# ET-AIO.net
KiCad netlist of a schematic drawn in Altium Designer
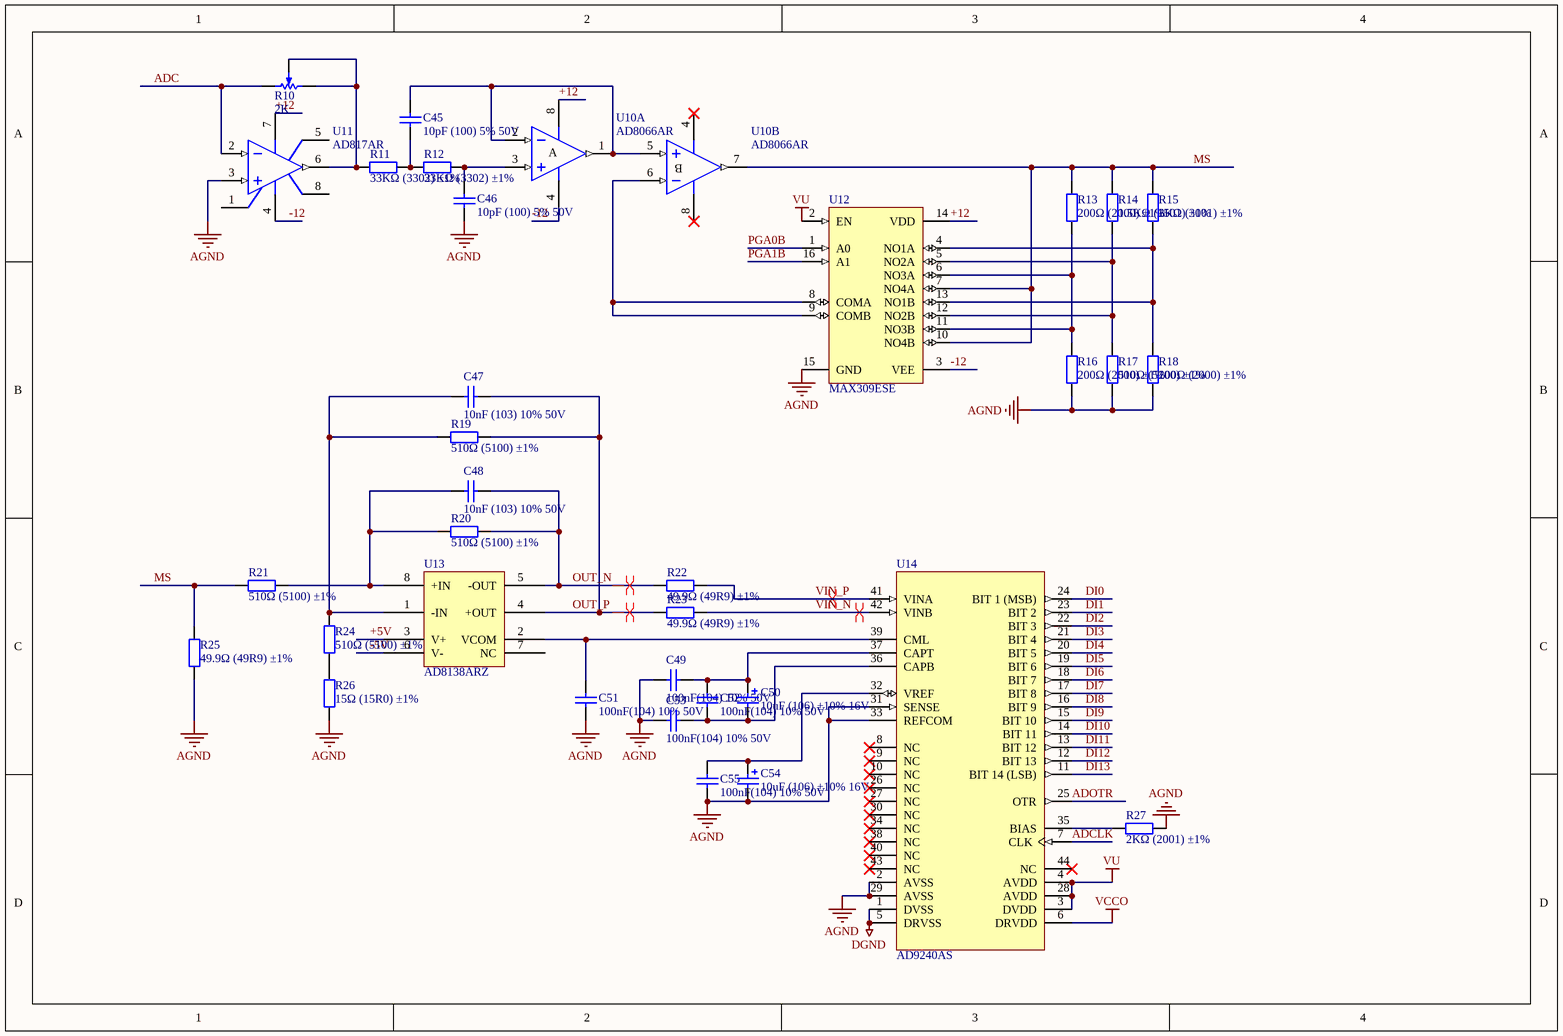
[diagram p0: ET-AIO.SchDoc]

(export (version "E")
  (design (tool "Eeschema 10.0.6"))
  (components
    (comp (ref "C45")
      (value "10pF (100) 5% 50V")
      (footprint "LC-0805_C")
      (description "贴片电容")
      (libsource (lib "Miscellaneous Devices LC") (part "0805 10pF (100) 5% 50V"))
    )
    (comp (ref "C46")
      (value "10pF (100) 5% 50V")
      (footprint "LC-0805_C")
      (description "贴片电容")
      (libsource (lib "Miscellaneous Devices LC") (part "0805 10pF (100) 5% 50V"))
    )
    (comp (ref "C47")
      (value "10nF (103) 10% 50V")
      (footprint "LC-0805_C")
      (description "贴片电容")
      (libsource (lib "Miscellaneous Devices LC") (part "0805 10nF (103) 10% 50V"))
    )
    (comp (ref "C48")
      (value "10nF (103) 10% 50V")
      (footprint "LC-0805_C")
      (description "贴片电容")
      (libsource (lib "Miscellaneous Devices LC") (part "0805 10nF (103) 10% 50V"))
    )
    (comp (ref "C49")
      (value "100nF(104) 10% 50V")
      (footprint "LC-0805_C")
      (description "贴片电容")
      (libsource (lib "Miscellaneous Devices LC") (part "0805 100nF(104) 10% 50V"))
    )
    (comp (ref "C50")
      (value "10uF (106) ±10% 16V")
      (footprint "LC-CASE-A_3216")
      (description "钽电容")
      (libsource (lib "Miscellaneous Devices LC") (part "3216 10uF (106) 10% 16V"))
    )
    (comp (ref "C51")
      (value "100nF(104) 10% 50V")
      (footprint "LC-0805_C")
      (description "贴片电容")
      (libsource (lib "Miscellaneous Devices LC") (part "0805 100nF(104) 10% 50V"))
    )
    (comp (ref "C52")
      (value "100nF(104) 10% 50V")
      (footprint "LC-0805_C")
      (description "贴片电容")
      (libsource (lib "Miscellaneous Devices LC") (part "0805 100nF(104) 10% 50V"))
    )
    (comp (ref "C53")
      (value "100nF(104) 10% 50V")
      (footprint "LC-0805_C")
      (description "贴片电容")
      (libsource (lib "Miscellaneous Devices LC") (part "0805 100nF(104) 10% 50V"))
    )
    (comp (ref "C54")
      (value "10uF (106) ±10% 16V")
      (footprint "LC-CASE-A_3216")
      (description "钽电容")
      (libsource (lib "Miscellaneous Devices LC") (part "3216 10uF (106) 10% 16V"))
    )
    (comp (ref "C55")
      (value "100nF(104) 10% 50V")
      (footprint "LC-0805_C")
      (description "贴片电容")
      (libsource (lib "Miscellaneous Devices LC") (part "0805 100nF(104) 10% 50V"))
    )
    (comp (ref "R10")
      (value "2K")
      (footprint "POT4MM-2")
      (description "Square Trimming Potentiometer")
      (fields (field (name "PUBLISHER") "Altium Limited"))
      (libsource (lib "Miscellaneous Devices") (part "RPot SM"))
    )
    (comp (ref "R11")
      (value "33KΩ (3302) ±1%")
      (footprint "LC-0805_R")
      (description "贴片电阻")
      (libsource (lib "Miscellaneous Devices LC") (part "0805 33KΩ (3302) 1%"))
    )
    (comp (ref "R12")
      (value "33KΩ (3302) ±1%")
      (footprint "LC-0805_R")
      (description "贴片电阻")
      (libsource (lib "Miscellaneous Devices LC") (part "0805 33KΩ (3302) 1%"))
    )
    (comp (ref "R13")
      (value "200Ω (2000) ±1%")
      (footprint "LC-0805_R")
      (description "贴片电阻")
      (libsource (lib "Miscellaneous Devices LC") (part "0805 200Ω (2000) 1%"))
    )
    (comp (ref "R14")
      (value "1.5KΩ (1501) ±1%")
      (footprint "LC-0805_R")
      (description "贴片电阻")
      (libsource (lib "Miscellaneous Devices LC") (part "0805 1.5KΩ (1501) 1%"))
    )
    (comp (ref "R15")
      (value "3KΩ (3001) ±1%")
      (footprint "LC-0805_R")
      (description "贴片电阻")
      (libsource (lib "Miscellaneous Devices LC") (part "0805 3KΩ (3001) 1%"))
    )
    (comp (ref "R16")
      (value "200Ω (2000) ±1%")
      (footprint "LC-0805_R")
      (description "贴片电阻")
      (libsource (lib "Miscellaneous Devices LC") (part "0805 200Ω (2000) 1%"))
    )
    (comp (ref "R17")
      (value "510Ω (5100) ±1%")
      (footprint "LC-0805_R")
      (description "贴片电阻")
      (libsource (lib "") (part "0805 510Ω (5100) 1%_1"))
    )
    (comp (ref "R18")
      (value "200Ω (2000) ±1%")
      (footprint "LC-0805_R")
      (description "贴片电阻")
      (libsource (lib "Miscellaneous Devices LC") (part "0805 200Ω (2000) 1%"))
    )
    (comp (ref "R19")
      (value "510Ω (5100) ±1%")
      (footprint "LC-0805_R")
      (description "贴片电阻")
      (libsource (lib "Miscellaneous Devices LC") (part "0805 510Ω (5100) 1%"))
    )
    (comp (ref "R20")
      (value "510Ω (5100) ±1%")
      (footprint "LC-0805_R")
      (description "贴片电阻")
      (libsource (lib "Miscellaneous Devices LC") (part "0805 510Ω (5100) 1%"))
    )
    (comp (ref "R21")
      (value "510Ω (5100) ±1%")
      (footprint "LC-0805_R")
      (description "贴片电阻")
      (libsource (lib "Miscellaneous Devices LC") (part "0805 510Ω (5100) 1%"))
    )
    (comp (ref "R22")
      (value "49.9Ω (49R9) ±1%")
      (footprint "LC-0805_R")
      (description "贴片电阻")
      (libsource (lib "Miscellaneous Devices LC") (part "0805 49.9Ω (49R9) 1%"))
    )
    (comp (ref "R23")
      (value "49.9Ω (49R9) ±1%")
      (footprint "LC-0805_R")
      (description "贴片电阻")
      (libsource (lib "Miscellaneous Devices LC") (part "0805 49.9Ω (49R9) 1%"))
    )
    (comp (ref "R24")
      (value "510Ω (5100) ±1%")
      (footprint "LC-0805_R")
      (description "贴片电阻")
      (libsource (lib "") (part "0805 510Ω (5100) 1%_1"))
    )
    (comp (ref "R25")
      (value "49.9Ω (49R9) ±1%")
      (footprint "LC-0805_R")
      (description "贴片电阻")
      (libsource (lib "") (part "0805 49.9Ω (49R9) 1%_1"))
    )
    (comp (ref "R26")
      (value "15Ω (15R0) ±1%")
      (footprint "LC-0805_R")
      (description "贴片电阻")
      (libsource (lib "Miscellaneous Devices LC") (part "0805 15Ω (15R0) 1%"))
    )
    (comp (ref "R27")
      (value "2KΩ (2001) ±1%")
      (footprint "LC-0805_R")
      (description "贴片电阻")
      (libsource (lib "Miscellaneous Devices LC") (part "0805 2KΩ (2001) 1%"))
    )
    (comp (ref "U10")
      (value "AD8066AR")
      (footprint "SO-8_N")
      (description "Low Cost, 300MHz Voltage Feedback Amplifier")
      (fields (field (name "PUBLISHER") "Altium Limited"))
      (libsource (lib "AD Operational Amplifier") (part "AD8056AR"))
    )
    (comp (ref "U11")
      (value "AD817AR")
      (footprint "mini-ET:SO-8_N")
      (description "High-Speed, Low-Power Wide Supply Range Amplifier")
      (fields (field (name "PUBLISHER") "Altium Limited"))
      (libsource (lib "AD Operational Amplifier") (part "AD817AR"))
    )
    (comp (ref "U12")
      (value "MAX309ESE")
      (footprint "mini-ET:NSO16_N")
      (description "Precision, Dual 4-Channel, High-Performance, CMOS Analog Multiplexer")
      (fields (field (name "PUBLISHER") "Altium Limited"))
      (libsource (lib "Maxim Logic Multiplexer") (part "MAX309ESE"))
    )
    (comp (ref "U13") (value "AD8138ARZ") (footprint "SO-8_N") (libsource (lib "AD8138") (part "AD8138ARZ")))
    (comp (ref "U14")
      (value "AD9240AS")
      (footprint "S-44-MQFP_N")
      (description "Complete 14-Bit, 10 MSPS Monolithic A/D Converter, 44-Pin MQFP, Industrial")
      (fields (field (name "PUBLISHER") "Altium Limited"))
      (libsource (lib "AD Converter Analog to Digital") (part "AD9240AS"))
    )
  )
  (nets
    (net (code "1") (name "/+5V") (class "Default")
      (node (ref "U13") (pin "3") (pinfunction "V+_3") (pintype "passive"))
    )
    (net (code "2") (name "/+12") (class "Default")
      (node (ref "U10") (pin "8") (pinfunction "V+_8") (pintype "power_in"))
      (node (ref "U11") (pin "7") (pinfunction "V+_7") (pintype "power_in"))
      (node (ref "U12") (pin "14") (pinfunction "VDD_14") (pintype "power_in"))
    )
    (net (code "3") (name "/-5V") (class "Default")
      (node (ref "U13") (pin "6") (pinfunction "V-_6") (pintype "passive"))
    )
    (net (code "4") (name "/-12") (class "Default")
      (node (ref "U10") (pin "4") (pinfunction "V-_4") (pintype "power_in"))
      (node (ref "U11") (pin "4") (pinfunction "V-_4") (pintype "power_in"))
      (node (ref "U12") (pin "3") (pinfunction "VEE_3") (pintype "power_in"))
    )
    (net (code "5") (name "/ADC") (class "Default")
      (node (ref "R10") (pin "CW") (pinfunction "+_CW") (pintype "passive"))
      (node (ref "U11") (pin "2") (pinfunction "IN-_2") (pintype "input"))
    )
    (net (code "6") (name "/ADCLK") (class "Default")
      (node (ref "U14") (pin "7") (pinfunction "CLK_7") (pintype "input"))
    )
    (net (code "7") (name "/ADOTR") (class "Default")
      (node (ref "U14") (pin "25") (pinfunction "OTR_25") (pintype "output"))
    )
    (net (code "8") (name "/DI0") (class "Default")
      (node (ref "U14") (pin "24") (pinfunction "BIT_1_(MSB)_24") (pintype "output"))
    )
    (net (code "9") (name "/DI1") (class "Default")
      (node (ref "U14") (pin "23") (pinfunction "BIT_2_23") (pintype "output"))
    )
    (net (code "10") (name "/DI2") (class "Default")
      (node (ref "U14") (pin "22") (pinfunction "BIT_3_22") (pintype "output"))
    )
    (net (code "11") (name "/DI3") (class "Default")
      (node (ref "U14") (pin "21") (pinfunction "BIT_4_21") (pintype "output"))
    )
    (net (code "12") (name "/DI4") (class "Default")
      (node (ref "U14") (pin "20") (pinfunction "BIT_5_20") (pintype "output"))
    )
    (net (code "13") (name "/DI5") (class "Default")
      (node (ref "U14") (pin "19") (pinfunction "BIT_6_19") (pintype "output"))
    )
    (net (code "14") (name "/DI6") (class "Default")
      (node (ref "U14") (pin "18") (pinfunction "BIT_7_18") (pintype "output"))
    )
    (net (code "15") (name "/DI7") (class "Default")
      (node (ref "U14") (pin "17") (pinfunction "BIT_8_17") (pintype "output"))
    )
    (net (code "16") (name "/DI8") (class "Default")
      (node (ref "U14") (pin "16") (pinfunction "BIT_9_16") (pintype "output"))
    )
    (net (code "17") (name "/DI9") (class "Default")
      (node (ref "U14") (pin "15") (pinfunction "BIT_10_15") (pintype "output"))
    )
    (net (code "18") (name "/DI10") (class "Default")
      (node (ref "U14") (pin "14") (pinfunction "BIT_11_14") (pintype "output"))
    )
    (net (code "19") (name "/DI11") (class "Default")
      (node (ref "U14") (pin "13") (pinfunction "BIT_12_13") (pintype "output"))
    )
    (net (code "20") (name "/DI12") (class "Default")
      (node (ref "U14") (pin "12") (pinfunction "BIT_13_12") (pintype "output"))
    )
    (net (code "21") (name "/DI13") (class "Default")
      (node (ref "U14") (pin "11") (pinfunction "BIT_14_(LSB)_11") (pintype "output"))
    )
    (net (code "22") (name "/MS") (class "Default")
      (node (ref "R13") (pin "2") (pinfunction "2_2") (pintype "passive"))
      (node (ref "R14") (pin "2") (pinfunction "2_2") (pintype "passive"))
      (node (ref "R15") (pin "2") (pinfunction "2_2") (pintype "passive"))
      (node (ref "R21") (pin "1") (pinfunction "1_1") (pintype "passive"))
      (node (ref "R25") (pin "2") (pinfunction "2_2") (pintype "passive"))
      (node (ref "U10") (pin "7") (pinfunction "OUT_7") (pintype "output"))
      (node (ref "U12") (pin "10") (pinfunction "NO4B_10") (pintype "bidirectional"))
      (node (ref "U12") (pin "7") (pinfunction "NO4A_7") (pintype "bidirectional"))
    )
    (net (code "23") (name "/OUT_N") (class "Default")
      (node (ref "C48") (pin "2") (pinfunction "2_2") (pintype "passive"))
      (node (ref "R20") (pin "2") (pinfunction "2_2") (pintype "passive"))
      (node (ref "R22") (pin "1") (pinfunction "1_1") (pintype "passive"))
      (node (ref "U13") (pin "5") (pinfunction "-OUT_5") (pintype "passive"))
    )
    (net (code "24") (name "/OUT_P") (class "Default")
      (node (ref "C47") (pin "2") (pinfunction "2_2") (pintype "passive"))
      (node (ref "R19") (pin "2") (pinfunction "2_2") (pintype "passive"))
      (node (ref "R23") (pin "1") (pinfunction "1_1") (pintype "passive"))
      (node (ref "U13") (pin "4") (pinfunction "+OUT_4") (pintype "passive"))
    )
    (net (code "25") (name "/PGA0B") (class "Default")
      (node (ref "U12") (pin "1") (pinfunction "A0_1") (pintype "input"))
    )
    (net (code "26") (name "/PGA1B") (class "Default")
      (node (ref "U12") (pin "16") (pinfunction "A1_16") (pintype "input"))
    )
    (net (code "27") (name "/VIN_N") (class "Default")
      (node (ref "R23") (pin "2") (pinfunction "2_2") (pintype "passive"))
      (node (ref "U14") (pin "42") (pinfunction "VINB_42") (pintype "input"))
    )
    (net (code "28") (name "/VIN_P") (class "Default")
      (node (ref "R22") (pin "2") (pinfunction "2_2") (pintype "passive"))
      (node (ref "U14") (pin "41") (pinfunction "VINA_41") (pintype "input"))
    )
    (net (code "29") (name "AGND") (class "Default")
      (node (ref "C46") (pin "1") (pinfunction "1_1") (pintype "passive"))
      (node (ref "C49") (pin "2") (pinfunction "2_2") (pintype "passive"))
      (node (ref "C51") (pin "1") (pinfunction "1_1") (pintype "passive"))
      (node (ref "C53") (pin "2") (pinfunction "2_2") (pintype "passive"))
      (node (ref "C54") (pin "2") (pinfunction "2_2") (pintype "passive"))
      (node (ref "C55") (pin "1") (pinfunction "1_1") (pintype "passive"))
      (node (ref "R16") (pin "1") (pinfunction "1_1") (pintype "passive"))
      (node (ref "R17") (pin "1") (pinfunction "1_1") (pintype "passive"))
      (node (ref "R18") (pin "1") (pinfunction "1_1") (pintype "passive"))
      (node (ref "R25") (pin "1") (pinfunction "1_1") (pintype "passive"))
      (node (ref "R26") (pin "1") (pinfunction "1_1") (pintype "passive"))
      (node (ref "R27") (pin "2") (pinfunction "2_2") (pintype "passive"))
      (node (ref "U11") (pin "3") (pinfunction "IN+_3") (pintype "input"))
      (node (ref "U12") (pin "15") (pinfunction "GND_15") (pintype "power_in"))
      (node (ref "U14") (pin "2") (pinfunction "AVSS_2") (pintype "power_in"))
      (node (ref "U14") (pin "29") (pinfunction "AVSS_29") (pintype "power_in"))
      (node (ref "U14") (pin "31") (pinfunction "SENSE_31") (pintype "input"))
      (node (ref "U14") (pin "33") (pinfunction "REFCOM_33") (pintype "power_in"))
    )
    (net (code "30") (name "DGND") (class "Default")
      (node (ref "U14") (pin "1") (pinfunction "DVSS_1") (pintype "power_in"))
      (node (ref "U14") (pin "5") (pinfunction "DRVSS_5") (pintype "power_in"))
    )
    (net (code "31") (name "Net-(C45-Pad1)") (class "Default")
      (node (ref "C45") (pin "1") (pinfunction "1_1") (pintype "passive"))
      (node (ref "R11") (pin "2") (pinfunction "2_2") (pintype "passive"))
      (node (ref "R12") (pin "1") (pinfunction "1_1") (pintype "passive"))
    )
    (net (code "32") (name "Net-(R10--)") (class "Default")
      (node (ref "R10") (pin "CCW") (pinfunction "-_CCW") (pintype "passive"))
      (node (ref "R10") (pin "W") (pinfunction "W_W") (pintype "passive"))
      (node (ref "R11") (pin "1") (pinfunction "1_1") (pintype "passive"))
      (node (ref "U11") (pin "6") (pinfunction "OUT_6") (pintype "output"))
    )
    (net (code "33") (name "Net-(R24-Pad1)") (class "Default")
      (node (ref "R24") (pin "1") (pinfunction "1_1") (pintype "passive"))
      (node (ref "R26") (pin "2") (pinfunction "2_2") (pintype "passive"))
    )
    (net (code "34") (name "Net-(U10A-IN+)") (class "Default")
      (node (ref "C46") (pin "2") (pinfunction "2_2") (pintype "passive"))
      (node (ref "R12") (pin "2") (pinfunction "2_2") (pintype "passive"))
      (node (ref "U10") (pin "3") (pinfunction "IN+_3") (pintype "input"))
    )
    (net (code "35") (name "Net-(U10A-IN-)") (class "Default")
      (node (ref "C45") (pin "2") (pinfunction "2_2") (pintype "passive"))
      (node (ref "U10") (pin "1") (pinfunction "OUT_1") (pintype "output"))
      (node (ref "U10") (pin "2") (pinfunction "IN-_2") (pintype "input"))
      (node (ref "U10") (pin "5") (pinfunction "IN+_5") (pintype "input"))
    )
    (net (code "36") (name "Net-(U10B-IN-)") (class "Default")
      (node (ref "U10") (pin "6") (pinfunction "IN-_6") (pintype "input"))
      (node (ref "U12") (pin "8") (pinfunction "COMA_8") (pintype "bidirectional"))
      (node (ref "U12") (pin "9") (pinfunction "COMB_9") (pintype "bidirectional"))
    )
    (net (code "37") (name "Net-(U12-NO1A)") (class "Default")
      (node (ref "R15") (pin "1") (pinfunction "1_1") (pintype "passive"))
      (node (ref "R18") (pin "2") (pinfunction "2_2") (pintype "passive"))
      (node (ref "U12") (pin "13") (pinfunction "NO1B_13") (pintype "bidirectional"))
      (node (ref "U12") (pin "4") (pinfunction "NO1A_4") (pintype "bidirectional"))
    )
    (net (code "38") (name "Net-(U12-NO2A)") (class "Default")
      (node (ref "R14") (pin "1") (pinfunction "1_1") (pintype "passive"))
      (node (ref "R17") (pin "2") (pinfunction "2_2") (pintype "passive"))
      (node (ref "U12") (pin "12") (pinfunction "NO2B_12") (pintype "bidirectional"))
      (node (ref "U12") (pin "5") (pinfunction "NO2A_5") (pintype "bidirectional"))
    )
    (net (code "39") (name "Net-(U12-NO3A)") (class "Default")
      (node (ref "R13") (pin "1") (pinfunction "1_1") (pintype "passive"))
      (node (ref "R16") (pin "2") (pinfunction "2_2") (pintype "passive"))
      (node (ref "U12") (pin "11") (pinfunction "NO3B_11") (pintype "bidirectional"))
      (node (ref "U12") (pin "6") (pinfunction "NO3A_6") (pintype "bidirectional"))
    )
    (net (code "40") (name "Net-(U13-+IN)") (class "Default")
      (node (ref "C48") (pin "1") (pinfunction "1_1") (pintype "passive"))
      (node (ref "R20") (pin "1") (pinfunction "1_1") (pintype "passive"))
      (node (ref "R21") (pin "2") (pinfunction "2_2") (pintype "passive"))
      (node (ref "U13") (pin "8") (pinfunction "+IN_8") (pintype "passive"))
    )
    (net (code "41") (name "Net-(U13--IN)") (class "Default")
      (node (ref "C47") (pin "1") (pinfunction "1_1") (pintype "passive"))
      (node (ref "R19") (pin "1") (pinfunction "1_1") (pintype "passive"))
      (node (ref "R24") (pin "2") (pinfunction "2_2") (pintype "passive"))
      (node (ref "U13") (pin "1") (pinfunction "-IN_1") (pintype "passive"))
    )
    (net (code "42") (name "Net-(U13-VCOM)") (class "Default")
      (node (ref "C51") (pin "2") (pinfunction "2_2") (pintype "passive"))
      (node (ref "U13") (pin "2") (pinfunction "VCOM_2") (pintype "passive"))
      (node (ref "U14") (pin "39") (pinfunction "CML_39") (pintype "power_in"))
    )
    (net (code "43") (name "Net-(U14-BIAS)") (class "Default")
      (node (ref "R27") (pin "1") (pinfunction "1_1") (pintype "passive"))
      (node (ref "U14") (pin "35") (pinfunction "BIAS_35") (pintype "passive"))
    )
    (net (code "44") (name "Net-(U14-CAPB)") (class "Default")
      (node (ref "C50") (pin "2") (pinfunction "2_2") (pintype "passive"))
      (node (ref "C52") (pin "1") (pinfunction "1_1") (pintype "passive"))
      (node (ref "C53") (pin "1") (pinfunction "1_1") (pintype "passive"))
      (node (ref "U14") (pin "36") (pinfunction "CAPB_36") (pintype "passive"))
    )
    (net (code "45") (name "Net-(U14-CAPT)") (class "Default")
      (node (ref "C49") (pin "1") (pinfunction "1_1") (pintype "passive"))
      (node (ref "C50") (pin "1") (pinfunction "1_1") (pintype "passive"))
      (node (ref "C52") (pin "2") (pinfunction "2_2") (pintype "passive"))
      (node (ref "U14") (pin "37") (pinfunction "CAPT_37") (pintype "passive"))
    )
    (net (code "46") (name "Net-(U14-VREF)") (class "Default")
      (node (ref "C54") (pin "1") (pinfunction "1_1") (pintype "passive"))
      (node (ref "C55") (pin "2") (pinfunction "2_2") (pintype "passive"))
      (node (ref "U14") (pin "32") (pinfunction "VREF_32") (pintype "bidirectional"))
    )
    (net (code "47") (name "VCCO") (class "Default")
      (node (ref "U14") (pin "6") (pinfunction "DRVDD_6") (pintype "power_in"))
    )
    (net (code "48") (name "VU") (class "Default")
      (node (ref "U12") (pin "2") (pinfunction "EN_2") (pintype "input"))
      (node (ref "U14") (pin "28") (pinfunction "AVDD_28") (pintype "power_in"))
      (node (ref "U14") (pin "3") (pinfunction "DVDD_3") (pintype "power_in"))
      (node (ref "U14") (pin "4") (pinfunction "AVDD_4") (pintype "power_in"))
    )
    (net (code "49") (name "unconnected-(U10B-V+-Pad8)") (class "Default")
      (node (ref "U10") (pin "8") (pinfunction "V+_8") (pintype "power_in+no_connect"))
    )
    (net (code "50") (name "unconnected-(U10B-V--Pad4)") (class "Default")
      (node (ref "U10") (pin "4") (pinfunction "V-_4") (pintype "power_in+no_connect"))
    )
    (net (code "51") (name "unconnected-(U11-NC-Pad5)") (class "Default")
      (node (ref "U11") (pin "5") (pinfunction "NC_5") (pintype "passive"))
    )
    (net (code "52") (name "unconnected-(U11-NULL1-Pad1)") (class "Default")
      (node (ref "U11") (pin "1") (pinfunction "NULL1_1") (pintype "passive"))
    )
    (net (code "53") (name "unconnected-(U11-NULL2-Pad8)") (class "Default")
      (node (ref "U11") (pin "8") (pinfunction "NULL2_8") (pintype "passive"))
    )
    (net (code "54") (name "unconnected-(U13-NC-Pad7)") (class "Default")
      (node (ref "U13") (pin "7") (pinfunction "NC_7") (pintype "passive"))
    )
    (net (code "55") (name "unconnected-(U14-NC-Pad8)") (class "Default")
      (node (ref "U14") (pin "8") (pinfunction "NC_8") (pintype "passive+no_connect"))
    )
    (net (code "56") (name "unconnected-(U14-NC-Pad9)") (class "Default")
      (node (ref "U14") (pin "9") (pinfunction "NC_9") (pintype "passive+no_connect"))
    )
    (net (code "57") (name "unconnected-(U14-NC-Pad10)") (class "Default")
      (node (ref "U14") (pin "10") (pinfunction "NC_10") (pintype "passive+no_connect"))
    )
    (net (code "58") (name "unconnected-(U14-NC-Pad26)") (class "Default")
      (node (ref "U14") (pin "26") (pinfunction "NC_26") (pintype "passive+no_connect"))
    )
    (net (code "59") (name "unconnected-(U14-NC-Pad27)") (class "Default")
      (node (ref "U14") (pin "27") (pinfunction "NC_27") (pintype "passive+no_connect"))
    )
    (net (code "60") (name "unconnected-(U14-NC-Pad30)") (class "Default")
      (node (ref "U14") (pin "30") (pinfunction "NC_30") (pintype "passive+no_connect"))
    )
    (net (code "61") (name "unconnected-(U14-NC-Pad34)") (class "Default")
      (node (ref "U14") (pin "34") (pinfunction "NC_34") (pintype "passive+no_connect"))
    )
    (net (code "62") (name "unconnected-(U14-NC-Pad38)") (class "Default")
      (node (ref "U14") (pin "38") (pinfunction "NC_38") (pintype "passive+no_connect"))
    )
    (net (code "63") (name "unconnected-(U14-NC-Pad40)") (class "Default")
      (node (ref "U14") (pin "40") (pinfunction "NC_40") (pintype "passive+no_connect"))
    )
    (net (code "64") (name "unconnected-(U14-NC-Pad43)") (class "Default")
      (node (ref "U14") (pin "43") (pinfunction "NC_43") (pintype "passive+no_connect"))
    )
    (net (code "65") (name "unconnected-(U14-NC-Pad44)") (class "Default")
      (node (ref "U14") (pin "44") (pinfunction "NC_44") (pintype "passive+no_connect"))
    )
  )
)
